# 04_4G.net
KiCad netlist of a schematic drawn in Altium Designer
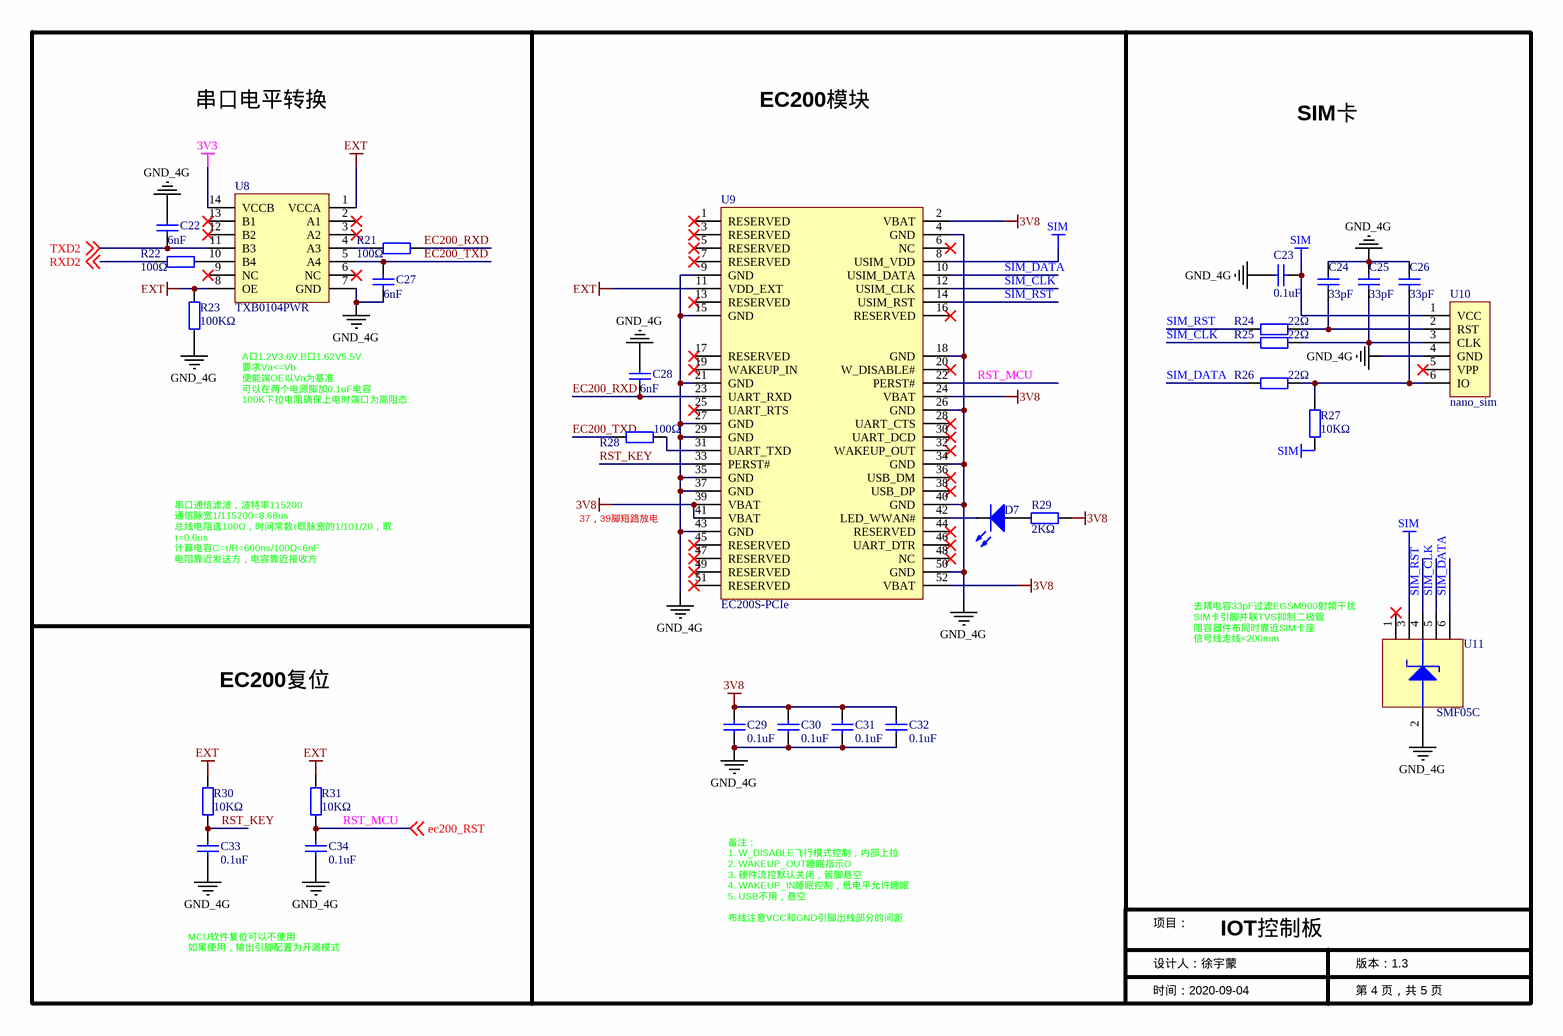
[diagram p0: 04_4G通信模块与外围电路.SchDoc]

(export (version "E")
  (design (tool "Eeschema 10.0.6"))
  (components
    (comp (ref "C22")
      (value "6nF")
      (footprint "CAP-0603")
      (description "无极性电容")
      (fields (field (name "Comment") "Cap") (field (name "PUBLISHER") "Altium Limited"))
      (libsource (lib "Arrowy_Racing") (part "Cap"))
    )
    (comp (ref "C23")
      (value "0.1uF")
      (footprint "CAP-0603")
      (description "无极性电容")
      (fields (field (name "Comment") "Cap") (field (name "PUBLISHER") "Altium Limited"))
      (libsource (lib "Arrowy_Racing") (part "Cap"))
    )
    (comp (ref "C24")
      (value "33pF")
      (footprint "CAP-0603")
      (description "无极性电容")
      (fields (field (name "Comment") "Cap") (field (name "PUBLISHER") "Altium Limited"))
      (libsource (lib "Arrowy_Racing") (part "Cap"))
    )
    (comp (ref "C25")
      (value "33pF")
      (footprint "CAP-0603")
      (description "无极性电容")
      (fields (field (name "Comment") "Cap") (field (name "PUBLISHER") "Altium Limited"))
      (libsource (lib "Arrowy_Racing") (part "Cap"))
    )
    (comp (ref "C26")
      (value "33pF")
      (footprint "CAP-0603")
      (description "无极性电容")
      (fields (field (name "Comment") "Cap") (field (name "PUBLISHER") "Altium Limited"))
      (libsource (lib "Arrowy_Racing") (part "Cap"))
    )
    (comp (ref "C27")
      (value "6nF")
      (footprint "CAP-0603")
      (description "无极性电容")
      (fields (field (name "Comment") "Cap") (field (name "PUBLISHER") "Altium Limited"))
      (libsource (lib "Arrowy_Racing") (part "Cap"))
    )
    (comp (ref "C28")
      (value "6nF")
      (footprint "CAP-0603")
      (description "无极性电容")
      (fields (field (name "Comment") "Cap") (field (name "PUBLISHER") "Altium Limited"))
      (libsource (lib "Arrowy_Racing") (part "Cap"))
    )
    (comp (ref "C29")
      (value "0.1uF")
      (footprint "CAP-0603")
      (description "无极性电容")
      (fields (field (name "Comment") "Cap") (field (name "PUBLISHER") "Altium Limited"))
      (libsource (lib "Arrowy_Racing") (part "Cap"))
    )
    (comp (ref "C30")
      (value "0.1uF")
      (footprint "CAP-0603")
      (description "无极性电容")
      (fields (field (name "Comment") "Cap") (field (name "PUBLISHER") "Altium Limited"))
      (libsource (lib "Arrowy_Racing") (part "Cap"))
    )
    (comp (ref "C31")
      (value "0.1uF")
      (footprint "CAP-0603")
      (description "无极性电容")
      (fields (field (name "Comment") "Cap") (field (name "PUBLISHER") "Altium Limited"))
      (libsource (lib "Arrowy_Racing") (part "Cap"))
    )
    (comp (ref "C32")
      (value "0.1uF")
      (footprint "CAP-0603")
      (description "无极性电容")
      (fields (field (name "Comment") "Cap") (field (name "PUBLISHER") "Altium Limited"))
      (libsource (lib "Arrowy_Racing") (part "Cap"))
    )
    (comp (ref "C33")
      (value "0.1uF")
      (footprint "CAP-0603")
      (description "无极性电容")
      (fields (field (name "Comment") "Cap") (field (name "PUBLISHER") "Altium Limited"))
      (libsource (lib "Arrowy_Racing") (part "Cap"))
    )
    (comp (ref "C34")
      (value "0.1uF")
      (footprint "CAP-0603")
      (description "无极性电容")
      (fields (field (name "Comment") "Cap") (field (name "PUBLISHER") "Altium Limited"))
      (libsource (lib "Arrowy_Racing") (part "Cap"))
    )
    (comp (ref "D7")
      (value "LED")
      (footprint "LED_0805")
      (description "发光二极管")
      (fields (field (name "PUBLISHER") "Altium Limited"))
      (libsource (lib "Arrowy_Racing") (part "LED"))
    )
    (comp (ref "R21")
      (value "100Ω")
      (footprint "0603")
      (description "贴片电阻")
      (fields (field (name "Comment") "Res") (field (name "PUBLISHER") "Altium Limited"))
      (libsource (lib "") (part "Res_1"))
    )
    (comp (ref "R22")
      (value "100Ω")
      (footprint "0603")
      (description "贴片电阻")
      (fields (field (name "Comment") "Res") (field (name "PUBLISHER") "Altium Limited"))
      (libsource (lib "") (part "Res_1"))
    )
    (comp (ref "R23")
      (value "100KΩ")
      (footprint "0603")
      (description "贴片电阻")
      (fields (field (name "Comment") "Res") (field (name "PUBLISHER") "Altium Limited"))
      (libsource (lib "Arrowy_Racing") (part "Res"))
    )
    (comp (ref "R24")
      (value "22Ω")
      (footprint "0603")
      (description "贴片电阻")
      (fields (field (name "Comment") "Res") (field (name "PUBLISHER") "Altium Limited"))
      (libsource (lib "Arrowy_Racing") (part "Res"))
    )
    (comp (ref "R25")
      (value "22Ω")
      (footprint "0603")
      (description "贴片电阻")
      (fields (field (name "Comment") "Res") (field (name "PUBLISHER") "Altium Limited"))
      (libsource (lib "Arrowy_Racing") (part "Res"))
    )
    (comp (ref "R26")
      (value "22Ω")
      (footprint "0603")
      (description "贴片电阻")
      (fields (field (name "Comment") "Res") (field (name "PUBLISHER") "Altium Limited"))
      (libsource (lib "Arrowy_Racing") (part "Res"))
    )
    (comp (ref "R27")
      (value "10KΩ")
      (footprint "0603")
      (description "贴片电阻")
      (fields (field (name "Comment") "Res") (field (name "PUBLISHER") "Altium Limited"))
      (libsource (lib "") (part "Res_1"))
    )
    (comp (ref "R28")
      (value "100Ω")
      (footprint "0603")
      (description "贴片电阻")
      (fields (field (name "Comment") "Res") (field (name "PUBLISHER") "Altium Limited"))
      (libsource (lib "") (part "Res_1"))
    )
    (comp (ref "R29")
      (value "2KΩ")
      (footprint "0603")
      (description "贴片电阻")
      (fields (field (name "Comment") "Res") (field (name "PUBLISHER") "Altium Limited"))
      (libsource (lib "") (part "Res_2"))
    )
    (comp (ref "R30")
      (value "10KΩ")
      (footprint "0603")
      (description "贴片电阻")
      (fields (field (name "Comment") "Res") (field (name "PUBLISHER") "Altium Limited"))
      (libsource (lib "") (part "Res_3"))
    )
    (comp (ref "R31")
      (value "10KΩ")
      (footprint "0603")
      (description "贴片电阻")
      (fields (field (name "Comment") "Res") (field (name "PUBLISHER") "Altium Limited"))
      (libsource (lib "") (part "Res_1"))
    )
    (comp (ref "U8")
      (value "TXB0104PWR")
      (footprint "TSSOP-14")
      (description "电平转换芯片")
      (libsource (lib "Arrowy_Racing") (part "TXB0104PWR"))
    )
    (comp (ref "U9")
      (value "EC200S-PCIe")
      (footprint "miniPCIe1")
      (libsource (lib "Arrowy_Racing") (part "EC200T-PCIe"))
    )
    (comp (ref "U10")
      (value "nano_sim")
      (footprint "Nano_SIM_6P")
      (libsource (lib "Arrowy_Racing") (part "nano_sim"))
    )
    (comp (ref "U11")
      (value "SMF05C")
      (footprint "SOT-363")
      (libsource (lib "Arrowy_Racing") (part "SMF05C"))
    )
  )
  (nets
    (net (code "1") (name "/EC200_RXD") (class "Default")
      (node (ref "C28") (pin "2") (pinfunction "2_2") (pintype "passive"))
      (node (ref "R21") (pin "1") (pinfunction "1_1") (pintype "passive"))
      (node (ref "U9") (pin "23") (pinfunction "UART_RXD_23") (pintype "passive"))
    )
    (net (code "2") (name "/EC200_TXD") (class "Default")
      (node (ref "C27") (pin "1") (pinfunction "1_1") (pintype "passive"))
      (node (ref "R28") (pin "2") (pinfunction "2_2") (pintype "passive"))
      (node (ref "U8") (pin "5") (pinfunction "A4_5") (pintype "passive"))
    )
    (net (code "3") (name "/RST_KEY") (class "Default")
      (node (ref "C33") (pin "2") (pinfunction "2_2") (pintype "passive"))
      (node (ref "R30") (pin "1") (pinfunction "1_1") (pintype "passive"))
      (node (ref "U9") (pin "33") (pinfunction "PERST#_33") (pintype "passive"))
    )
    (net (code "4") (name "/SIM_CLK") (class "Default")
      (node (ref "R25") (pin "1") (pinfunction "1_1") (pintype "passive"))
      (node (ref "U11") (pin "5") (pinfunction "gnd_5") (pintype "passive"))
      (node (ref "U9") (pin "12") (pinfunction "USIM_CLK_12") (pintype "passive"))
    )
    (net (code "5") (name "/SIM_DATA") (class "Default")
      (node (ref "R26") (pin "1") (pinfunction "1_1") (pintype "passive"))
      (node (ref "U11") (pin "6") (pinfunction "gnd_6") (pintype "passive"))
      (node (ref "U9") (pin "10") (pinfunction "USIM_DATA_10") (pintype "passive"))
    )
    (net (code "6") (name "/SIM_RST") (class "Default")
      (node (ref "R24") (pin "1") (pinfunction "1_1") (pintype "passive"))
      (node (ref "U11") (pin "4") (pinfunction "gnd_4") (pintype "passive"))
      (node (ref "U9") (pin "14") (pinfunction "USIM_RST_14") (pintype "passive"))
    )
    (net (code "7") (name "3V3") (class "Default")
      (node (ref "U8") (pin "14") (pinfunction "VCCB_14") (pintype "passive"))
    )
    (net (code "8") (name "3V8") (class "Default")
      (node (ref "C29") (pin "2") (pinfunction "2_2") (pintype "passive"))
      (node (ref "C30") (pin "2") (pinfunction "2_2") (pintype "passive"))
      (node (ref "C31") (pin "2") (pinfunction "2_2") (pintype "passive"))
      (node (ref "C32") (pin "2") (pinfunction "2_2") (pintype "passive"))
      (node (ref "R29") (pin "1") (pinfunction "1_1") (pintype "passive"))
      (node (ref "U9") (pin "2") (pinfunction "VBAT_2") (pintype "passive"))
      (node (ref "U9") (pin "24") (pinfunction "VBAT_24") (pintype "passive"))
      (node (ref "U9") (pin "39") (pinfunction "VBAT_39") (pintype "passive"))
      (node (ref "U9") (pin "41") (pinfunction "VBAT_41") (pintype "passive"))
      (node (ref "U9") (pin "52") (pinfunction "VBAT_52") (pintype "passive"))
    )
    (net (code "9") (name "EXT") (class "Default")
      (node (ref "R23") (pin "2") (pinfunction "2_2") (pintype "passive"))
      (node (ref "R30") (pin "2") (pinfunction "2_2") (pintype "passive"))
      (node (ref "R31") (pin "1") (pinfunction "1_1") (pintype "passive"))
      (node (ref "U8") (pin "1") (pinfunction "VCCA_1") (pintype "passive"))
      (node (ref "U8") (pin "8") (pinfunction "OE_8") (pintype "passive"))
      (node (ref "U9") (pin "11") (pinfunction "VDD_EXT_11") (pintype "passive"))
    )
    (net (code "10") (name "GND_4G") (class "Default")
      (node (ref "C22") (pin "1") (pinfunction "1_1") (pintype "passive"))
      (node (ref "C23") (pin "2") (pinfunction "2_2") (pintype "passive"))
      (node (ref "C24") (pin "1") (pinfunction "1_1") (pintype "passive"))
      (node (ref "C25") (pin "1") (pinfunction "1_1") (pintype "passive"))
      (node (ref "C26") (pin "2") (pinfunction "2_2") (pintype "passive"))
      (node (ref "C27") (pin "2") (pinfunction "2_2") (pintype "passive"))
      (node (ref "C28") (pin "1") (pinfunction "1_1") (pintype "passive"))
      (node (ref "C29") (pin "1") (pinfunction "1_1") (pintype "passive"))
      (node (ref "C30") (pin "1") (pinfunction "1_1") (pintype "passive"))
      (node (ref "C31") (pin "1") (pinfunction "1_1") (pintype "passive"))
      (node (ref "C32") (pin "1") (pinfunction "1_1") (pintype "passive"))
      (node (ref "C33") (pin "1") (pinfunction "1_1") (pintype "passive"))
      (node (ref "C34") (pin "2") (pinfunction "2_2") (pintype "passive"))
      (node (ref "R23") (pin "1") (pinfunction "1_1") (pintype "passive"))
      (node (ref "U10") (pin "4") (pinfunction "GND_4") (pintype "passive"))
      (node (ref "U11") (pin "2") (pinfunction "gnd_2") (pintype "passive"))
      (node (ref "U8") (pin "7") (pinfunction "GND_7") (pintype "passive"))
      (node (ref "U9") (pin "15") (pinfunction "GND_15") (pintype "passive"))
      (node (ref "U9") (pin "18") (pinfunction "GND_18") (pintype "passive"))
      (node (ref "U9") (pin "21") (pinfunction "GND_21") (pintype "passive"))
      (node (ref "U9") (pin "26") (pinfunction "GND_26") (pintype "passive"))
      (node (ref "U9") (pin "27") (pinfunction "GND_27") (pintype "passive"))
      (node (ref "U9") (pin "29") (pinfunction "GND_29") (pintype "passive"))
      (node (ref "U9") (pin "34") (pinfunction "GND_34") (pintype "passive"))
      (node (ref "U9") (pin "35") (pinfunction "GND_35") (pintype "passive"))
      (node (ref "U9") (pin "37") (pinfunction "GND_37") (pintype "passive"))
      (node (ref "U9") (pin "4") (pinfunction "GND_4") (pintype "passive"))
      (node (ref "U9") (pin "40") (pinfunction "GND_40") (pintype "passive"))
      (node (ref "U9") (pin "43") (pinfunction "GND_43") (pintype "passive"))
      (node (ref "U9") (pin "50") (pinfunction "GND_50") (pintype "passive"))
      (node (ref "U9") (pin "9") (pinfunction "GND_9") (pintype "passive"))
    )
    (net (code "11") (name "Net-(D7-A)") (class "Default")
      (node (ref "D7") (pin "1") (pinfunction "A_1") (pintype "passive"))
      (node (ref "R29") (pin "2") (pinfunction "2_2") (pintype "passive"))
    )
    (net (code "12") (name "Net-(D7-K)") (class "Default")
      (node (ref "D7") (pin "2") (pinfunction "K_2") (pintype "passive"))
      (node (ref "U9") (pin "42") (pinfunction "LED_WWAN#_42") (pintype "passive"))
    )
    (net (code "13") (name "Net-(U8-A3)") (class "Default")
      (node (ref "R21") (pin "2") (pinfunction "2_2") (pintype "passive"))
      (node (ref "U8") (pin "4") (pinfunction "A3_4") (pintype "passive"))
    )
    (net (code "14") (name "Net-(U8-B4)") (class "Default")
      (node (ref "R22") (pin "1") (pinfunction "1_1") (pintype "passive"))
      (node (ref "U8") (pin "10") (pinfunction "B4_10") (pintype "passive"))
    )
    (net (code "15") (name "Net-(U9-UART_TXD)") (class "Default")
      (node (ref "R28") (pin "1") (pinfunction "1_1") (pintype "passive"))
      (node (ref "U9") (pin "31") (pinfunction "UART_TXD_31") (pintype "passive"))
    )
    (net (code "16") (name "Net-(U10-CLK)") (class "Default")
      (node (ref "C25") (pin "2") (pinfunction "2_2") (pintype "passive"))
      (node (ref "R25") (pin "2") (pinfunction "2_2") (pintype "passive"))
      (node (ref "U10") (pin "3") (pinfunction "CLK_3") (pintype "passive"))
    )
    (net (code "17") (name "Net-(U10-IO)") (class "Default")
      (node (ref "C26") (pin "1") (pinfunction "1_1") (pintype "passive"))
      (node (ref "R26") (pin "2") (pinfunction "2_2") (pintype "passive"))
      (node (ref "R27") (pin "1") (pinfunction "1_1") (pintype "passive"))
      (node (ref "U10") (pin "6") (pinfunction "IO_6") (pintype "passive"))
    )
    (net (code "18") (name "Net-(U10-RST)") (class "Default")
      (node (ref "C24") (pin "2") (pinfunction "2_2") (pintype "passive"))
      (node (ref "R24") (pin "2") (pinfunction "2_2") (pintype "passive"))
      (node (ref "U10") (pin "2") (pinfunction "RST_2") (pintype "passive"))
    )
    (net (code "19") (name "RXD2") (class "Default")
      (node (ref "R22") (pin "2") (pinfunction "2_2") (pintype "passive"))
    )
    (net (code "20") (name "SIM") (class "Default")
      (node (ref "C23") (pin "1") (pinfunction "1_1") (pintype "passive"))
      (node (ref "R27") (pin "2") (pinfunction "2_2") (pintype "passive"))
      (node (ref "U10") (pin "1") (pinfunction "VCC_1") (pintype "passive"))
      (node (ref "U11") (pin "3") (pinfunction "gnd_3") (pintype "passive"))
      (node (ref "U9") (pin "8") (pinfunction "USIM_VDD_8") (pintype "passive"))
    )
    (net (code "21") (name "TXD2") (class "Default")
      (node (ref "C22") (pin "2") (pinfunction "2_2") (pintype "passive"))
      (node (ref "U8") (pin "11") (pinfunction "B3_11") (pintype "passive"))
    )
    (net (code "22") (name "ec200_RST") (class "Default")
      (node (ref "C34") (pin "1") (pinfunction "1_1") (pintype "passive"))
      (node (ref "R31") (pin "2") (pinfunction "2_2") (pintype "passive"))
      (node (ref "U9") (pin "22") (pinfunction "PERST#_22") (pintype "passive"))
    )
    (net (code "23") (name "unconnected-(U8-A1-Pad2)") (class "Default")
      (node (ref "U8") (pin "2") (pinfunction "A1_2") (pintype "passive+no_connect"))
    )
    (net (code "24") (name "unconnected-(U8-A2-Pad3)") (class "Default")
      (node (ref "U8") (pin "3") (pinfunction "A2_3") (pintype "passive+no_connect"))
    )
    (net (code "25") (name "unconnected-(U8-B1-Pad13)") (class "Default")
      (node (ref "U8") (pin "13") (pinfunction "B1_13") (pintype "passive+no_connect"))
    )
    (net (code "26") (name "unconnected-(U8-B2-Pad12)") (class "Default")
      (node (ref "U8") (pin "12") (pinfunction "B2_12") (pintype "passive+no_connect"))
    )
    (net (code "27") (name "unconnected-(U8-NC-Pad6)") (class "Default")
      (node (ref "U8") (pin "6") (pinfunction "NC_6") (pintype "passive+no_connect"))
    )
    (net (code "28") (name "unconnected-(U8-NC-Pad9)") (class "Default")
      (node (ref "U8") (pin "9") (pinfunction "NC_9") (pintype "passive+no_connect"))
    )
    (net (code "29") (name "unconnected-(U9-NC-Pad6)") (class "Default")
      (node (ref "U9") (pin "6") (pinfunction "NC_6") (pintype "passive+no_connect"))
    )
    (net (code "30") (name "unconnected-(U9-NC-Pad48)") (class "Default")
      (node (ref "U9") (pin "48") (pinfunction "NC_48") (pintype "passive+no_connect"))
    )
    (net (code "31") (name "unconnected-(U9-RESERVED-Pad1)") (class "Default")
      (node (ref "U9") (pin "1") (pinfunction "RESERVED_1") (pintype "passive+no_connect"))
    )
    (net (code "32") (name "unconnected-(U9-RESERVED-Pad3)") (class "Default")
      (node (ref "U9") (pin "3") (pinfunction "RESERVED_3") (pintype "passive+no_connect"))
    )
    (net (code "33") (name "unconnected-(U9-RESERVED-Pad5)") (class "Default")
      (node (ref "U9") (pin "5") (pinfunction "RESERVED_5") (pintype "passive+no_connect"))
    )
    (net (code "34") (name "unconnected-(U9-RESERVED-Pad7)") (class "Default")
      (node (ref "U9") (pin "7") (pinfunction "RESERVED_7") (pintype "passive+no_connect"))
    )
    (net (code "35") (name "unconnected-(U9-RESERVED-Pad13)") (class "Default")
      (node (ref "U9") (pin "13") (pinfunction "RESERVED_13") (pintype "passive+no_connect"))
    )
    (net (code "36") (name "unconnected-(U9-RESERVED-Pad16)") (class "Default")
      (node (ref "U9") (pin "16") (pinfunction "RESERVED_16") (pintype "passive+no_connect"))
    )
    (net (code "37") (name "unconnected-(U9-RESERVED-Pad17)") (class "Default")
      (node (ref "U9") (pin "17") (pinfunction "RESERVED_17") (pintype "passive+no_connect"))
    )
    (net (code "38") (name "unconnected-(U9-RESERVED-Pad44)") (class "Default")
      (node (ref "U9") (pin "44") (pinfunction "RESERVED_44") (pintype "passive+no_connect"))
    )
    (net (code "39") (name "unconnected-(U9-RESERVED-Pad45)") (class "Default")
      (node (ref "U9") (pin "45") (pinfunction "RESERVED_45") (pintype "passive+no_connect"))
    )
    (net (code "40") (name "unconnected-(U9-RESERVED-Pad47)") (class "Default")
      (node (ref "U9") (pin "47") (pinfunction "RESERVED_47") (pintype "passive+no_connect"))
    )
    (net (code "41") (name "unconnected-(U9-RESERVED-Pad49)") (class "Default")
      (node (ref "U9") (pin "49") (pinfunction "RESERVED_49") (pintype "passive+no_connect"))
    )
    (net (code "42") (name "unconnected-(U9-RESERVED-Pad51)") (class "Default")
      (node (ref "U9") (pin "51") (pinfunction "RESERVED_51") (pintype "passive+no_connect"))
    )
    (net (code "43") (name "unconnected-(U9-UART_CTS-Pad28)") (class "Default")
      (node (ref "U9") (pin "28") (pinfunction "UART_CTS_28") (pintype "passive+no_connect"))
    )
    (net (code "44") (name "unconnected-(U9-UART_DCD-Pad30)") (class "Default")
      (node (ref "U9") (pin "30") (pinfunction "UART_DCD_30") (pintype "passive+no_connect"))
    )
    (net (code "45") (name "unconnected-(U9-UART_DTR-Pad46)") (class "Default")
      (node (ref "U9") (pin "46") (pinfunction "UART_DTR_46") (pintype "passive+no_connect"))
    )
    (net (code "46") (name "unconnected-(U9-UART_RTS-Pad25)") (class "Default")
      (node (ref "U9") (pin "25") (pinfunction "UART_RTS_25") (pintype "passive+no_connect"))
    )
    (net (code "47") (name "unconnected-(U9-USB_DM-Pad36)") (class "Default")
      (node (ref "U9") (pin "36") (pinfunction "USB_DM_36") (pintype "passive+no_connect"))
    )
    (net (code "48") (name "unconnected-(U9-USB_DP-Pad38)") (class "Default")
      (node (ref "U9") (pin "38") (pinfunction "USB_DP_38") (pintype "passive+no_connect"))
    )
    (net (code "49") (name "unconnected-(U9-WAKEUP_IN-Pad19)") (class "Default")
      (node (ref "U9") (pin "19") (pinfunction "WAKEUP_IN_19") (pintype "passive+no_connect"))
    )
    (net (code "50") (name "unconnected-(U9-WAKEUP_OUT-Pad32)") (class "Default")
      (node (ref "U9") (pin "32") (pinfunction "WAKEUP_OUT_32") (pintype "passive+no_connect"))
    )
    (net (code "51") (name "unconnected-(U9-W_DISABLE#-Pad20)") (class "Default")
      (node (ref "U9") (pin "20") (pinfunction "W_DISABLE#_20") (pintype "passive+no_connect"))
    )
    (net (code "52") (name "unconnected-(U10-VPP-Pad5)") (class "Default")
      (node (ref "U10") (pin "5") (pinfunction "VPP_5") (pintype "passive+no_connect"))
    )
    (net (code "53") (name "unconnected-(U11-gnd-Pad1)") (class "Default")
      (node (ref "U11") (pin "1") (pinfunction "gnd_1") (pintype "passive+no_connect"))
    )
  )
)
